# nled-ws2801-fet-v1b.net
KiCad netlist of a schematic drawn in EAGLE
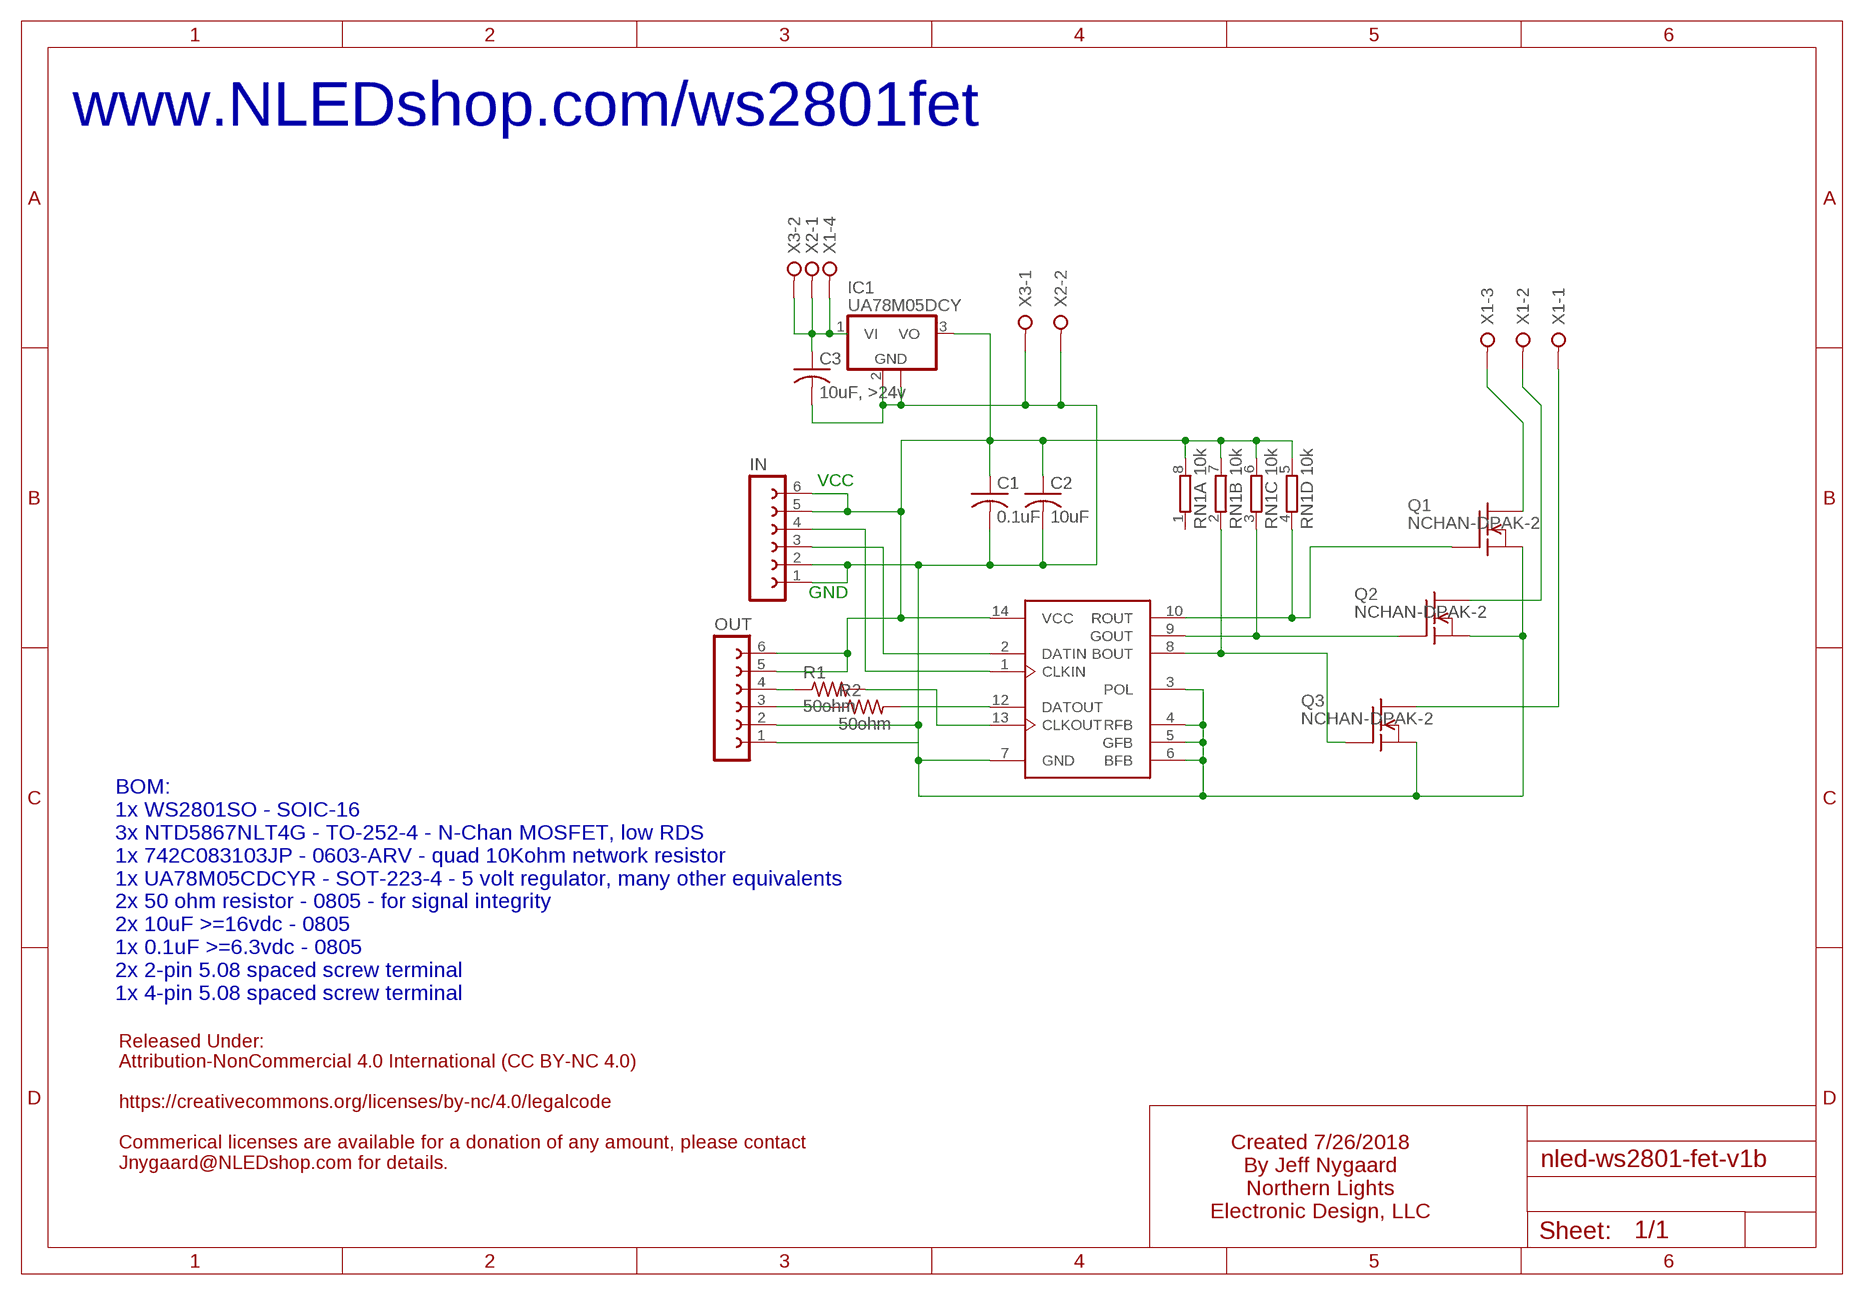
[diagram p0: schematic, sheet 1]

(export (version "E")
  (design (tool "Eeschema 10.0.6"))
  (components
    (comp (ref "C1")
      (value "0.1uF")
      (footprint "eagle-import:C1206")
      (libsource (lib "eagle-import") (part "C-USC1206"))
    )
    (comp (ref "C2")
      (value "10uF")
      (footprint "eagle-import:C1206")
      (libsource (lib "eagle-import") (part "C-USC1206"))
    )
    (comp (ref "C3")
      (value "10uF, >24v")
      (footprint "eagle-import:C1206")
      (libsource (lib "eagle-import") (part "C-USC1206"))
    )
    (comp (ref "IC1")
      (value "UA78M05DCY")
      (footprint "eagle-import:SOT223")
      (libsource (lib "eagle-import") (part "UA78MDCY05"))
    )
    (comp (ref "IN")
      (value "FE06-1")
      (footprint "eagle-import:FE06")
      (fields (field (name "OC_FARNELL") "unknown") (field (name "OC_NEWARK") "unknown"))
      (libsource (lib "eagle-import") (part "FE06-1"))
    )
    (comp (ref "OUT")
      (value "FE06-1")
      (footprint "eagle-import:FE06")
      (libsource (lib "eagle-import") (part "FE06-1"))
    )
    (comp (ref "Q1")
      (value "NCHAN-DPAK-2")
      (footprint "eagle-import:DPAK-2PIN")
      (libsource (lib "eagle-import") (part "NCHAN-DPAK-2"))
    )
    (comp (ref "Q2")
      (value "NCHAN-DPAK-2")
      (footprint "eagle-import:DPAK-2PIN")
      (libsource (lib "eagle-import") (part "NCHAN-DPAK-2"))
    )
    (comp (ref "Q3")
      (value "NCHAN-DPAK-2")
      (footprint "eagle-import:DPAK-2PIN")
      (libsource (lib "eagle-import") (part "NCHAN-DPAK-2"))
    )
    (comp (ref "R1")
      (value "50ohm")
      (footprint "eagle-import:M0805")
      (libsource (lib "eagle-import") (part "R-US_M0805"))
    )
    (comp (ref "R2")
      (value "50ohm")
      (footprint "eagle-import:M0805")
      (libsource (lib "eagle-import") (part "R-US_M0805"))
    )
    (comp (ref "RN1")
      (value "10k")
      (footprint "eagle-import:0603-ARV")
      (libsource (lib "eagle-import") (part "4R-N0603-ARV"))
    )
    (comp (ref "WS2801")
      (value "WS2801")
      (footprint "eagle-import:SOP14")
      (libsource (lib "eagle-import") (part "WS2801"))
    )
    (comp (ref "X1")
      (value "W237-04P")
      (footprint "eagle-import:W237-4P")
      (libsource (lib "eagle-import") (part "W237-04P"))
    )
    (comp (ref "X2")
      (value "W237-02P")
      (footprint "eagle-import:W237-132")
      (libsource (lib "eagle-import") (part "W237-02P"))
    )
    (comp (ref "X3")
      (value "W237-02P")
      (footprint "eagle-import:W237-132")
      (libsource (lib "eagle-import") (part "W237-02P"))
    )
  )
  (nets
    (net (code "1") (name "Net-(IC1-VI)") (class "Default")
      (node (ref "C3") (pin "1") (pinfunction "1_1") (pintype "passive"))
      (node (ref "IC1") (pin "1") (pinfunction "VI_1") (pintype "input"))
      (node (ref "X1") (pin "4") (pinfunction "KL_4") (pintype "passive"))
      (node (ref "X2") (pin "1") (pinfunction "KL_1") (pintype "passive"))
      (node (ref "X3") (pin "2") (pinfunction "KL_2") (pintype "passive"))
    )
    (net (code "2") (name "Net-(IC1-VO)") (class "Default")
      (node (ref "C1") (pin "1") (pinfunction "1_1") (pintype "passive"))
      (node (ref "C2") (pin "1") (pinfunction "1_1") (pintype "passive"))
      (node (ref "IC1") (pin "3") (pinfunction "VO_3") (pintype "passive"))
      (node (ref "IN") (pin "5") (pinfunction "5_5") (pintype "passive"))
      (node (ref "IN") (pin "6") (pinfunction "6_6") (pintype "passive"))
      (node (ref "OUT") (pin "5") (pinfunction "5_5") (pintype "passive"))
      (node (ref "OUT") (pin "6") (pinfunction "6_6") (pintype "passive"))
      (node (ref "RN1") (pin "5") (pinfunction "2_5") (pintype "passive"))
      (node (ref "RN1") (pin "6") (pinfunction "2_6") (pintype "passive"))
      (node (ref "RN1") (pin "7") (pinfunction "2_7") (pintype "passive"))
      (node (ref "RN1") (pin "8") (pinfunction "2_8") (pintype "passive"))
      (node (ref "WS2801") (pin "14") (pinfunction "VCC_14") (pintype "bidirectional"))
    )
    (net (code "3") (name "Net-(OUT-Pad3)") (class "Default")
      (node (ref "OUT") (pin "3") (pinfunction "3_3") (pintype "passive"))
      (node (ref "R2") (pin "1") (pinfunction "1_1") (pintype "passive"))
    )
    (net (code "4") (name "Net-(OUT-Pad4)") (class "Default")
      (node (ref "OUT") (pin "4") (pinfunction "4_4") (pintype "passive"))
      (node (ref "R1") (pin "1") (pinfunction "1_1") (pintype "passive"))
    )
    (net (code "5") (name "Net-(Q1-D)") (class "Default")
      (node (ref "Q1") (pin "2") (pinfunction "D_2") (pintype "passive"))
      (node (ref "X1") (pin "3") (pinfunction "KL_3") (pintype "passive"))
    )
    (net (code "6") (name "Net-(Q1-G)") (class "Default")
      (node (ref "Q1") (pin "1") (pinfunction "G_1") (pintype "passive"))
      (node (ref "RN1") (pin "4") (pinfunction "1_4") (pintype "passive"))
      (node (ref "WS2801") (pin "10") (pinfunction "ROUT_10") (pintype "bidirectional"))
    )
    (net (code "7") (name "Net-(Q1-S)") (class "Default")
      (node (ref "C1") (pin "2") (pinfunction "2_2") (pintype "passive"))
      (node (ref "C2") (pin "2") (pinfunction "2_2") (pintype "passive"))
      (node (ref "C3") (pin "2") (pinfunction "2_2") (pintype "passive"))
      (node (ref "IC1") (pin "2") (pinfunction "GND_2") (pintype "passive"))
      (node (ref "IC1") (pin "4") (pinfunction "GND_4") (pintype "passive"))
      (node (ref "IN") (pin "1") (pinfunction "1_1") (pintype "passive"))
      (node (ref "IN") (pin "2") (pinfunction "2_2") (pintype "passive"))
      (node (ref "OUT") (pin "1") (pinfunction "1_1") (pintype "passive"))
      (node (ref "OUT") (pin "2") (pinfunction "2_2") (pintype "passive"))
      (node (ref "Q1") (pin "3") (pinfunction "S_3") (pintype "passive"))
      (node (ref "Q2") (pin "3") (pinfunction "S_3") (pintype "passive"))
      (node (ref "Q3") (pin "3") (pinfunction "S_3") (pintype "passive"))
      (node (ref "WS2801") (pin "3") (pinfunction "POL_3") (pintype "bidirectional"))
      (node (ref "WS2801") (pin "4") (pinfunction "RFB_4") (pintype "bidirectional"))
      (node (ref "WS2801") (pin "5") (pinfunction "GFB_5") (pintype "bidirectional"))
      (node (ref "WS2801") (pin "6") (pinfunction "BFB_6") (pintype "bidirectional"))
      (node (ref "WS2801") (pin "7") (pinfunction "GND_7") (pintype "bidirectional"))
      (node (ref "X2") (pin "2") (pinfunction "KL_2") (pintype "passive"))
      (node (ref "X3") (pin "1") (pinfunction "KL_1") (pintype "passive"))
    )
    (net (code "8") (name "Net-(Q2-D)") (class "Default")
      (node (ref "Q2") (pin "2") (pinfunction "D_2") (pintype "passive"))
      (node (ref "X1") (pin "2") (pinfunction "KL_2") (pintype "passive"))
    )
    (net (code "9") (name "Net-(Q2-G)") (class "Default")
      (node (ref "Q2") (pin "1") (pinfunction "G_1") (pintype "passive"))
      (node (ref "RN1") (pin "3") (pinfunction "1_3") (pintype "passive"))
      (node (ref "WS2801") (pin "9") (pinfunction "GOUT_9") (pintype "bidirectional"))
    )
    (net (code "10") (name "Net-(Q3-D)") (class "Default")
      (node (ref "Q3") (pin "2") (pinfunction "D_2") (pintype "passive"))
      (node (ref "X1") (pin "1") (pinfunction "KL_1") (pintype "passive"))
    )
    (net (code "11") (name "Net-(Q3-G)") (class "Default")
      (node (ref "Q3") (pin "1") (pinfunction "G_1") (pintype "passive"))
      (node (ref "RN1") (pin "2") (pinfunction "1_2") (pintype "passive"))
      (node (ref "WS2801") (pin "8") (pinfunction "BOUT_8") (pintype "bidirectional"))
    )
    (net (code "12") (name "Net-(WS2801-CLKIN)") (class "Default")
      (node (ref "IN") (pin "4") (pinfunction "4_4") (pintype "passive"))
      (node (ref "WS2801") (pin "1") (pinfunction "CLKIN_1") (pintype "bidirectional"))
    )
    (net (code "13") (name "Net-(WS2801-CLKOUT)") (class "Default")
      (node (ref "R1") (pin "2") (pinfunction "2_2") (pintype "passive"))
      (node (ref "WS2801") (pin "13") (pinfunction "CLKOUT_13") (pintype "bidirectional"))
    )
    (net (code "14") (name "Net-(WS2801-DATIN)") (class "Default")
      (node (ref "IN") (pin "3") (pinfunction "3_3") (pintype "passive"))
      (node (ref "WS2801") (pin "2") (pinfunction "DATIN_2") (pintype "bidirectional"))
    )
    (net (code "15") (name "Net-(WS2801-DATOUT)") (class "Default")
      (node (ref "R2") (pin "2") (pinfunction "2_2") (pintype "passive"))
      (node (ref "WS2801") (pin "12") (pinfunction "DATOUT_12") (pintype "bidirectional"))
    )
    (net (code "16") (name "unconnected-(RN1-Pad1)") (class "Default")
      (node (ref "RN1") (pin "1") (pinfunction "1_1") (pintype "passive"))
    )
  )
)
